# squall-breakout.net
KiCad netlist of a schematic drawn in EAGLE
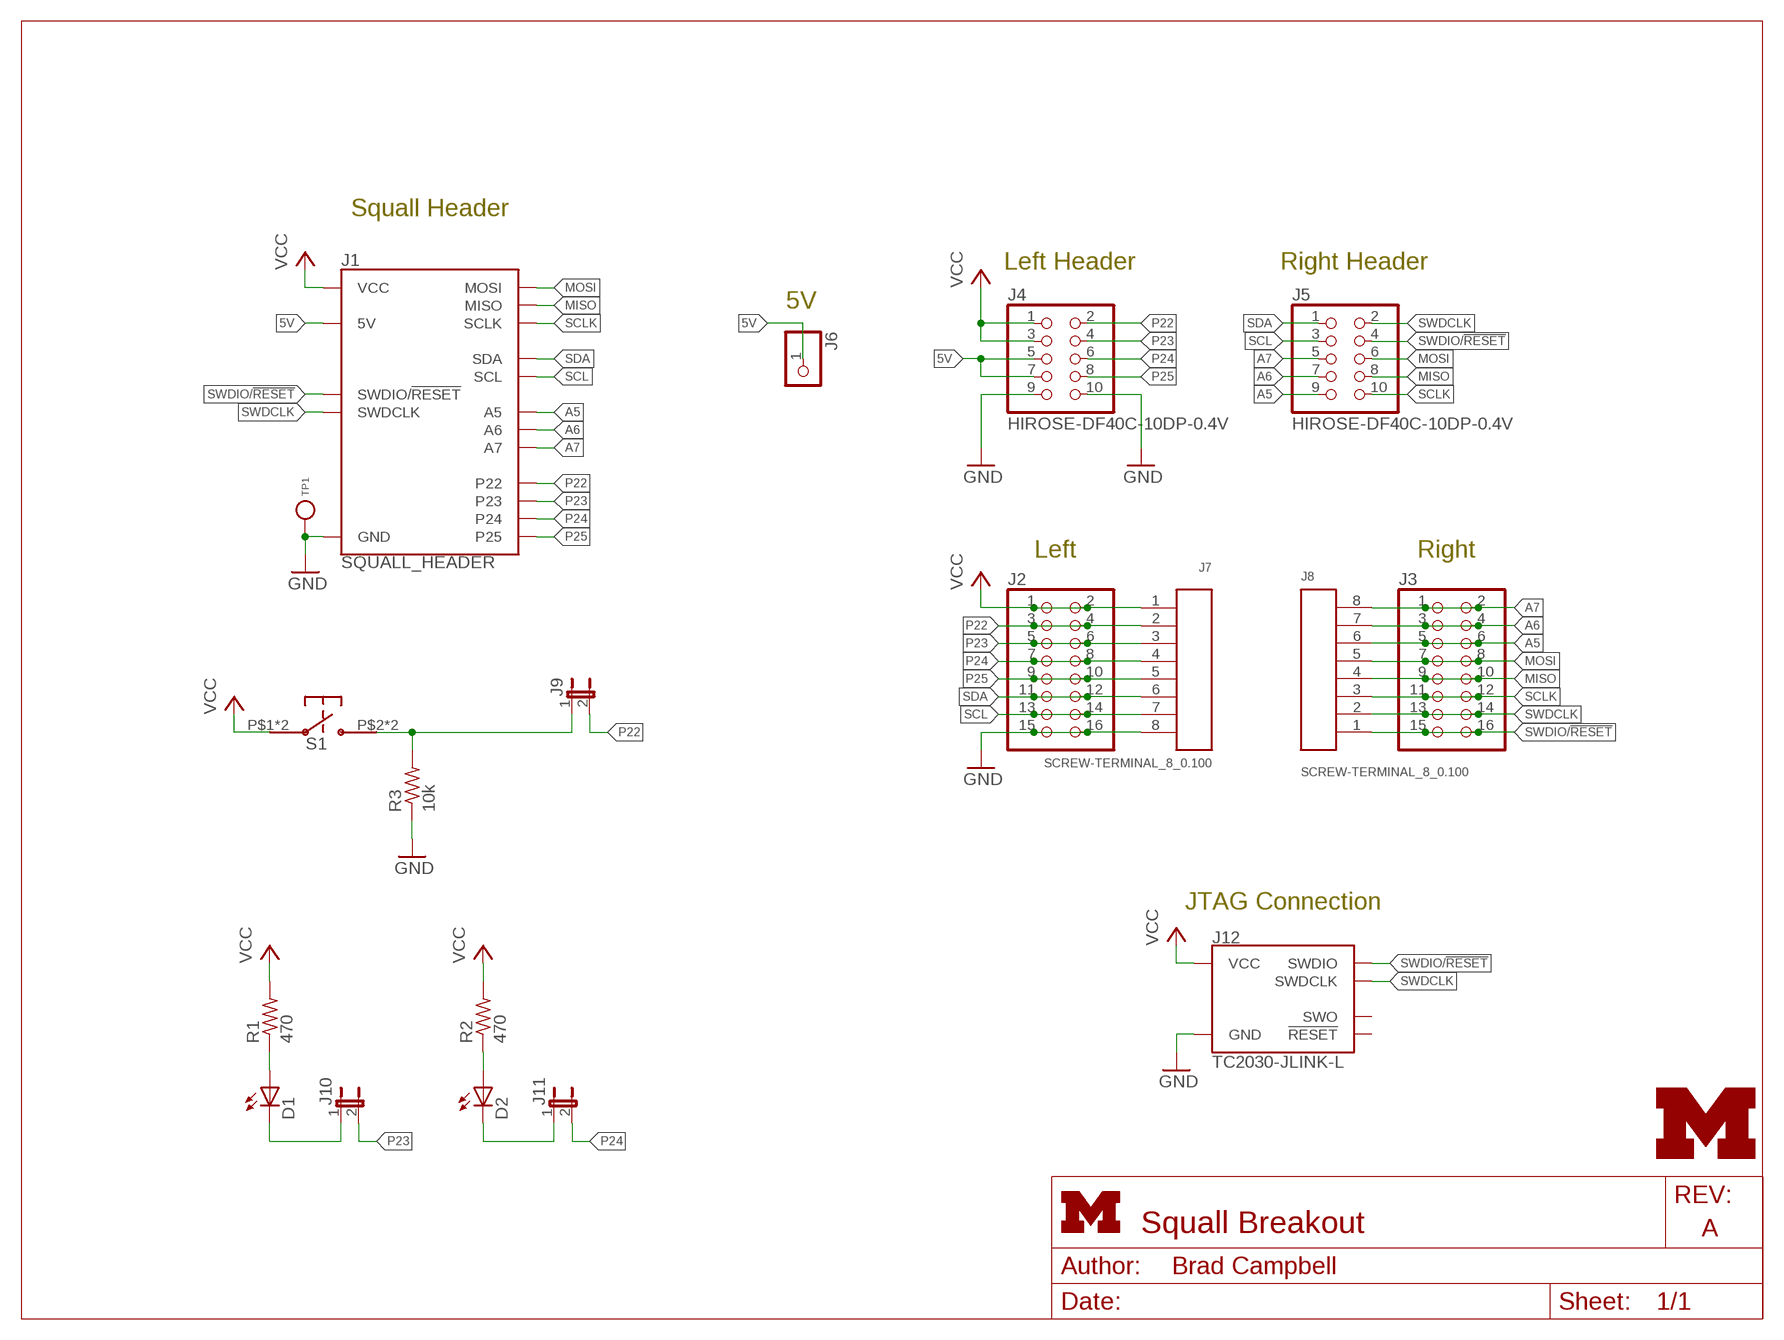
[diagram p0: schematic, sheet 1]

(export (version "E")
  (design (tool "Eeschema 10.0.6"))
  (components
    (comp (ref "D1")
      (value "LED0603")
      (footprint "eagle-import:LED-0603")
      (libsource (lib "eagle-import") (part "LED0603"))
    )
    (comp (ref "D2")
      (value "LED0603")
      (footprint "eagle-import:LED-0603")
      (libsource (lib "eagle-import") (part "LED0603"))
    )
    (comp (ref "J1")
      (value "SQUALL_HEADER")
      (footprint "eagle-import:SQUALL_HEADER")
      (libsource (lib "eagle-import") (part "SQUALL_HEADER"))
    )
    (comp (ref "J2")
      (value "PINHD-2X8")
      (footprint "eagle-import:2X08")
      (libsource (lib "eagle-import") (part "PINHD-2X8"))
    )
    (comp (ref "J3")
      (value "PINHD-2X8")
      (footprint "eagle-import:2X08")
      (libsource (lib "eagle-import") (part "PINHD-2X8"))
    )
    (comp (ref "J4")
      (value "HIROSE-DF40C-10DP-0.4V")
      (footprint "eagle-import:2X5_SMD_0.4MM")
      (libsource (lib "eagle-import") (part "HIROSE-DF40C-10DP-0.4V"))
    )
    (comp (ref "J5")
      (value "HIROSE-DF40C-10DP-0.4V")
      (footprint "eagle-import:2X5_SMD_0.4MM")
      (libsource (lib "eagle-import") (part "HIROSE-DF40C-10DP-0.4V"))
    )
    (comp (ref "J6")
      (value "PINHD-1X1")
      (footprint "eagle-import:1X01")
      (libsource (lib "eagle-import") (part "PINHD-1X1"))
    )
    (comp (ref "J7")
      (value "SCREW-TERMINAL_8_0.100")
      (footprint "eagle-import:CONN_BLOCK_8")
      (libsource (lib "eagle-import") (part "SCREW-TERMINAL_8_0.100"))
    )
    (comp (ref "J8")
      (value "SCREW-TERMINAL_8_0.100")
      (footprint "eagle-import:CONN_BLOCK_8")
      (libsource (lib "eagle-import") (part "SCREW-TERMINAL_8_0.100"))
    )
    (comp (ref "J9")
      (value "JUMPER-2PTH")
      (footprint "eagle-import:1X02")
      (libsource (lib "eagle-import") (part "JUMPER-2PTH"))
    )
    (comp (ref "J10")
      (value "JUMPER-2PTH")
      (footprint "eagle-import:1X02")
      (libsource (lib "eagle-import") (part "JUMPER-2PTH"))
    )
    (comp (ref "J11")
      (value "JUMPER-2PTH")
      (footprint "eagle-import:1X02")
      (libsource (lib "eagle-import") (part "JUMPER-2PTH"))
    )
    (comp (ref "J12")
      (value "TC2030-JLINK-L")
      (footprint "eagle-import:TC2030-IDC")
      (libsource (lib "eagle-import") (part "TC2030-JLINK-L"))
    )
    (comp (ref "LOGO1")
      (value "UMICH_SOLID_TINY")
      (footprint "eagle-import:UMICH_SOLID_50MIL")
      (libsource (lib "eagle-import") (part "UMICH_SOLID_TINY"))
    )
    (comp (ref "R1")
      (value "470")
      (footprint "eagle-import:R0603")
      (libsource (lib "eagle-import") (part "R-US_R0603"))
    )
    (comp (ref "R2")
      (value "470")
      (footprint "eagle-import:R0603")
      (libsource (lib "eagle-import") (part "R-US_R0603"))
    )
    (comp (ref "R3")
      (value "10k")
      (footprint "eagle-import:R0603")
      (libsource (lib "eagle-import") (part "R-US_R0603"))
    )
    (comp (ref "S1")
      (value "EVQP2")
      (footprint "eagle-import:EVQP2")
      (libsource (lib "eagle-import") (part "EVQP2"))
    )
    (comp (ref "TP1")
      (value "TEST_POINT_0.112IN")
      (footprint "eagle-import:TESTPOINT_0.112IN")
      (libsource (lib "eagle-import") (part "TEST_POINT_0.112IN"))
    )
  )
  (nets
    (net (code "1") (name "/SWDIO{slash}~{RESET}") (class "Default")
      (node (ref "J1") (pin "B4") (pinfunction "SWDIO/~{RESET}_B4") (pintype "bidirectional"))
      (node (ref "J12") (pin "2") (pinfunction "SWDIO_2") (pintype "bidirectional"))
      (node (ref "J3") (pin "15") (pinfunction "15_15") (pintype "passive"))
      (node (ref "J3") (pin "16") (pinfunction "16_16") (pintype "passive"))
      (node (ref "J5") (pin "4") (pinfunction "4_4") (pintype "passive"))
      (node (ref "J8") (pin "1") (pinfunction "1_1") (pintype "bidirectional"))
    )
    (net (code "2") (name "5V") (class "Default")
      (node (ref "J1") (pin "A5") (pinfunction "5V_A5") (pintype "bidirectional"))
      (node (ref "J1") (pin "A7") (pinfunction "5V_A7") (pintype "bidirectional"))
      (node (ref "J4") (pin "5") (pinfunction "5_5") (pintype "passive"))
      (node (ref "J4") (pin "7") (pinfunction "7_7") (pintype "passive"))
      (node (ref "J6") (pin "1") (pinfunction "1_1") (pintype "passive"))
    )
    (net (code "3") (name "A5") (class "Default")
      (node (ref "J1") (pin "B9") (pinfunction "A5_B9") (pintype "bidirectional"))
      (node (ref "J3") (pin "5") (pinfunction "5_5") (pintype "passive"))
      (node (ref "J3") (pin "6") (pinfunction "6_6") (pintype "passive"))
      (node (ref "J5") (pin "9") (pinfunction "9_9") (pintype "passive"))
      (node (ref "J8") (pin "6") (pinfunction "6_6") (pintype "bidirectional"))
    )
    (net (code "4") (name "A6") (class "Default")
      (node (ref "J1") (pin "B7") (pinfunction "A6_B7") (pintype "bidirectional"))
      (node (ref "J3") (pin "3") (pinfunction "3_3") (pintype "passive"))
      (node (ref "J3") (pin "4") (pinfunction "4_4") (pintype "passive"))
      (node (ref "J5") (pin "7") (pinfunction "7_7") (pintype "passive"))
      (node (ref "J8") (pin "7") (pinfunction "7_7") (pintype "bidirectional"))
    )
    (net (code "5") (name "A7") (class "Default")
      (node (ref "J1") (pin "B5") (pinfunction "A7_B5") (pintype "bidirectional"))
      (node (ref "J3") (pin "1") (pinfunction "1_1") (pintype "passive"))
      (node (ref "J3") (pin "2") (pinfunction "2_2") (pintype "passive"))
      (node (ref "J5") (pin "5") (pinfunction "5_5") (pintype "passive"))
      (node (ref "J8") (pin "8") (pinfunction "8_8") (pintype "bidirectional"))
    )
    (net (code "6") (name "GND") (class "Default")
      (node (ref "J1") (pin "A10") (pinfunction "GND_A10") (pintype "bidirectional"))
      (node (ref "J1") (pin "A9") (pinfunction "GND_A9") (pintype "bidirectional"))
      (node (ref "J12") (pin "5") (pinfunction "GND_5") (pintype "bidirectional"))
      (node (ref "J2") (pin "15") (pinfunction "15_15") (pintype "passive"))
      (node (ref "J2") (pin "16") (pinfunction "16_16") (pintype "passive"))
      (node (ref "J4") (pin "10") (pinfunction "10_10") (pintype "passive"))
      (node (ref "J4") (pin "9") (pinfunction "9_9") (pintype "passive"))
      (node (ref "J7") (pin "8") (pinfunction "8_8") (pintype "bidirectional"))
      (node (ref "R3") (pin "1") (pinfunction "1_1") (pintype "passive"))
      (node (ref "TP1") (pin "1") (pinfunction "TESTPOINT_1") (pintype "bidirectional"))
    )
    (net (code "7") (name "MISO") (class "Default")
      (node (ref "J1") (pin "B8") (pinfunction "MISO_B8") (pintype "bidirectional"))
      (node (ref "J3") (pin "10") (pinfunction "10_10") (pintype "passive"))
      (node (ref "J3") (pin "9") (pinfunction "9_9") (pintype "passive"))
      (node (ref "J5") (pin "8") (pinfunction "8_8") (pintype "passive"))
      (node (ref "J8") (pin "4") (pinfunction "4_4") (pintype "bidirectional"))
    )
    (net (code "8") (name "MOSI") (class "Default")
      (node (ref "J1") (pin "B6") (pinfunction "MOSI_B6") (pintype "bidirectional"))
      (node (ref "J3") (pin "7") (pinfunction "7_7") (pintype "passive"))
      (node (ref "J3") (pin "8") (pinfunction "8_8") (pintype "passive"))
      (node (ref "J5") (pin "6") (pinfunction "6_6") (pintype "passive"))
      (node (ref "J8") (pin "5") (pinfunction "5_5") (pintype "bidirectional"))
    )
    (net (code "9") (name "Net-(D1-PadA)") (class "Default")
      (node (ref "D1") (pin "A") (pinfunction "A_A") (pintype "passive"))
      (node (ref "R1") (pin "1") (pinfunction "1_1") (pintype "passive"))
    )
    (net (code "10") (name "Net-(D1-PadC)") (class "Default")
      (node (ref "D1") (pin "C") (pinfunction "C_C") (pintype "passive"))
      (node (ref "J10") (pin "1") (pinfunction "1_1") (pintype "passive"))
    )
    (net (code "11") (name "Net-(D2-PadA)") (class "Default")
      (node (ref "D2") (pin "A") (pinfunction "A_A") (pintype "passive"))
      (node (ref "R2") (pin "1") (pinfunction "1_1") (pintype "passive"))
    )
    (net (code "12") (name "Net-(D2-PadC)") (class "Default")
      (node (ref "D2") (pin "C") (pinfunction "C_C") (pintype "passive"))
      (node (ref "J11") (pin "1") (pinfunction "1_1") (pintype "passive"))
    )
    (net (code "13") (name "Net-(J9-Pad1)") (class "Default")
      (node (ref "J9") (pin "1") (pinfunction "1_1") (pintype "passive"))
      (node (ref "R3") (pin "2") (pinfunction "2_2") (pintype "passive"))
      (node (ref "S1") (pin "P$2") (pinfunction "P$2_P$2") (pintype "passive"))
      (node (ref "S1") (pin "P$4") (pinfunction "P$2_P$4") (pintype "passive"))
    )
    (net (code "14") (name "P22") (class "Default")
      (node (ref "J1") (pin "A2") (pinfunction "P22_A2") (pintype "bidirectional"))
      (node (ref "J2") (pin "3") (pinfunction "3_3") (pintype "passive"))
      (node (ref "J2") (pin "4") (pinfunction "4_4") (pintype "passive"))
      (node (ref "J4") (pin "2") (pinfunction "2_2") (pintype "passive"))
      (node (ref "J7") (pin "2") (pinfunction "2_2") (pintype "bidirectional"))
      (node (ref "J9") (pin "2") (pinfunction "2_2") (pintype "passive"))
    )
    (net (code "15") (name "P23") (class "Default")
      (node (ref "J1") (pin "A4") (pinfunction "P23_A4") (pintype "bidirectional"))
      (node (ref "J10") (pin "2") (pinfunction "2_2") (pintype "passive"))
      (node (ref "J2") (pin "5") (pinfunction "5_5") (pintype "passive"))
      (node (ref "J2") (pin "6") (pinfunction "6_6") (pintype "passive"))
      (node (ref "J4") (pin "4") (pinfunction "4_4") (pintype "passive"))
      (node (ref "J7") (pin "3") (pinfunction "3_3") (pintype "bidirectional"))
    )
    (net (code "16") (name "P24") (class "Default")
      (node (ref "J1") (pin "A6") (pinfunction "P24_A6") (pintype "bidirectional"))
      (node (ref "J11") (pin "2") (pinfunction "2_2") (pintype "passive"))
      (node (ref "J2") (pin "7") (pinfunction "7_7") (pintype "passive"))
      (node (ref "J2") (pin "8") (pinfunction "8_8") (pintype "passive"))
      (node (ref "J4") (pin "6") (pinfunction "6_6") (pintype "passive"))
      (node (ref "J7") (pin "4") (pinfunction "4_4") (pintype "bidirectional"))
    )
    (net (code "17") (name "P25") (class "Default")
      (node (ref "J1") (pin "A8") (pinfunction "P25_A8") (pintype "bidirectional"))
      (node (ref "J2") (pin "10") (pinfunction "10_10") (pintype "passive"))
      (node (ref "J2") (pin "9") (pinfunction "9_9") (pintype "passive"))
      (node (ref "J4") (pin "8") (pinfunction "8_8") (pintype "passive"))
      (node (ref "J7") (pin "5") (pinfunction "5_5") (pintype "bidirectional"))
    )
    (net (code "18") (name "SCL") (class "Default")
      (node (ref "J1") (pin "B3") (pinfunction "SCL_B3") (pintype "bidirectional"))
      (node (ref "J2") (pin "13") (pinfunction "13_13") (pintype "passive"))
      (node (ref "J2") (pin "14") (pinfunction "14_14") (pintype "passive"))
      (node (ref "J5") (pin "3") (pinfunction "3_3") (pintype "passive"))
      (node (ref "J7") (pin "7") (pinfunction "7_7") (pintype "bidirectional"))
    )
    (net (code "19") (name "SCLK") (class "Default")
      (node (ref "J1") (pin "B10") (pinfunction "SCLK_B10") (pintype "bidirectional"))
      (node (ref "J3") (pin "11") (pinfunction "11_11") (pintype "passive"))
      (node (ref "J3") (pin "12") (pinfunction "12_12") (pintype "passive"))
      (node (ref "J5") (pin "10") (pinfunction "10_10") (pintype "passive"))
      (node (ref "J8") (pin "3") (pinfunction "3_3") (pintype "bidirectional"))
    )
    (net (code "20") (name "SDA") (class "Default")
      (node (ref "J1") (pin "B1") (pinfunction "SDA_B1") (pintype "bidirectional"))
      (node (ref "J2") (pin "11") (pinfunction "11_11") (pintype "passive"))
      (node (ref "J2") (pin "12") (pinfunction "12_12") (pintype "passive"))
      (node (ref "J5") (pin "1") (pinfunction "1_1") (pintype "passive"))
      (node (ref "J7") (pin "6") (pinfunction "6_6") (pintype "bidirectional"))
    )
    (net (code "21") (name "SWDCLK") (class "Default")
      (node (ref "J1") (pin "B2") (pinfunction "SWDCLK_B2") (pintype "bidirectional"))
      (node (ref "J12") (pin "4") (pinfunction "SWDCLK_4") (pintype "bidirectional"))
      (node (ref "J3") (pin "13") (pinfunction "13_13") (pintype "passive"))
      (node (ref "J3") (pin "14") (pinfunction "14_14") (pintype "passive"))
      (node (ref "J5") (pin "2") (pinfunction "2_2") (pintype "passive"))
      (node (ref "J8") (pin "2") (pinfunction "2_2") (pintype "bidirectional"))
    )
    (net (code "22") (name "VCC") (class "Default")
      (node (ref "J1") (pin "A1") (pinfunction "VCC_A1") (pintype "bidirectional"))
      (node (ref "J1") (pin "A3") (pinfunction "VCC_A3") (pintype "bidirectional"))
      (node (ref "J12") (pin "1") (pinfunction "VCC_1") (pintype "bidirectional"))
      (node (ref "J2") (pin "1") (pinfunction "1_1") (pintype "passive"))
      (node (ref "J2") (pin "2") (pinfunction "2_2") (pintype "passive"))
      (node (ref "J4") (pin "1") (pinfunction "1_1") (pintype "passive"))
      (node (ref "J4") (pin "3") (pinfunction "3_3") (pintype "passive"))
      (node (ref "J7") (pin "1") (pinfunction "1_1") (pintype "bidirectional"))
      (node (ref "R1") (pin "2") (pinfunction "2_2") (pintype "passive"))
      (node (ref "R2") (pin "2") (pinfunction "2_2") (pintype "passive"))
      (node (ref "S1") (pin "P$1") (pinfunction "P$1_P$1") (pintype "passive"))
      (node (ref "S1") (pin "P$3") (pinfunction "P$1_P$3") (pintype "passive"))
    )
    (net (code "23") (name "unconnected-(J12-SWO-Pad6)") (class "Default")
      (node (ref "J12") (pin "6") (pinfunction "SWO_6") (pintype "bidirectional"))
    )
    (net (code "24") (name "unconnected-(J12-~{RESET}-Pad3)") (class "Default")
      (node (ref "J12") (pin "3") (pinfunction "~{RESET}_3") (pintype "bidirectional"))
    )
  )
)
